# EagleSchematic.net
KiCad netlist of a schematic drawn in EAGLE
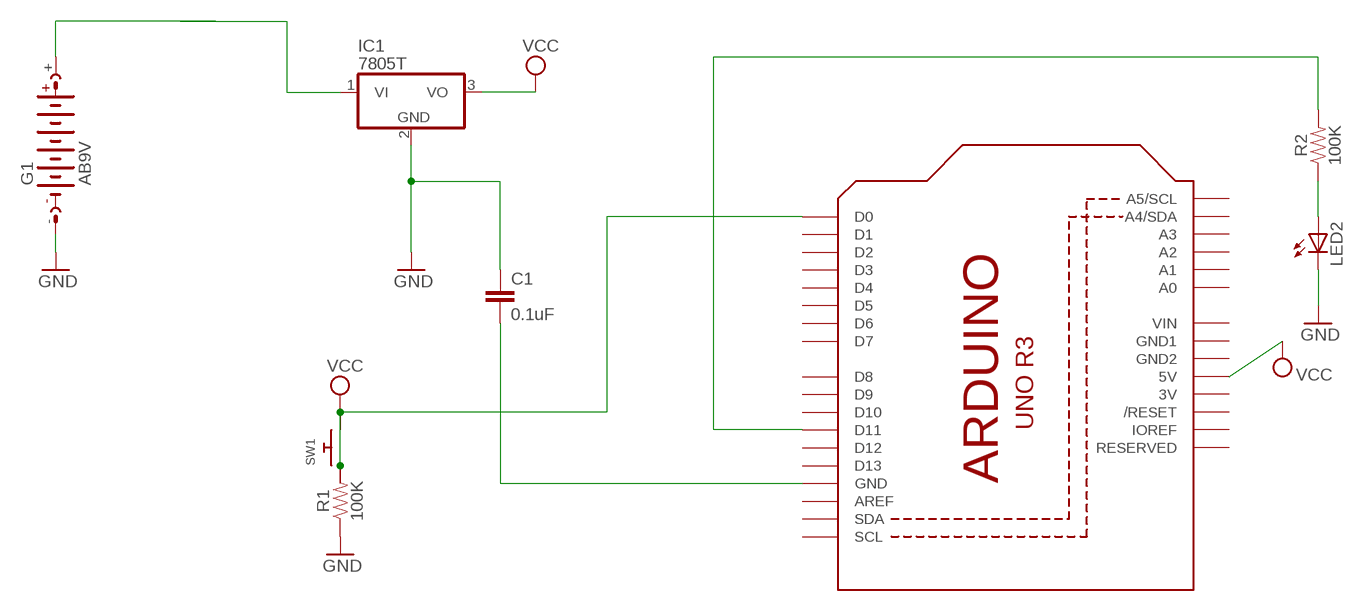
[diagram p0: schematic, sheet 1]

(export (version "E")
  (design (tool "Eeschema 10.0.6"))
  (components
    (comp (ref "C1")
      (value "0.1uF")
      (footprint "eagle-import:0402")
      (libsource (lib "eagle-import") (part "0.1UF-0402-16V-10%"))
    )
    (comp (ref "G1")
      (value "AB9V")
      (footprint "eagle-import:AB9V")
      (libsource (lib "eagle-import") (part "AB9V"))
    )
    (comp (ref "IC1")
      (value "7805T")
      (footprint "eagle-import:TO220H")
      (libsource (lib "eagle-import") (part "78T05"))
    )
    (comp (ref "LED2")
      (value "LED5MM")
      (footprint "eagle-import:LED5MM")
      (libsource (lib "eagle-import") (part "LED5MM"))
    )
    (comp (ref "R1")
      (value "100K")
      (footprint "eagle-import:0402")
      (libsource (lib "eagle-import") (part "100KOHM-0402-1/16W-1%"))
    )
    (comp (ref "R2")
      (value "100K")
      (footprint "eagle-import:0402")
      (libsource (lib "eagle-import") (part "100KOHM-0402-1/16W-1%"))
    )
    (comp (ref "SW1")
      (value "SWITCH_PUSHBUTTONSOFTTOUCHSMD_SJ")
      (footprint "eagle-import:PUSHBUTTON_SMD_SJ")
      (libsource (lib "eagle-import") (part "SWITCH_PUSHBUTTONSOFTTOUCHSMD_SJ"))
    )
    (comp (ref "U1")
      (value "ARDUINOR3-BPLACE")
      (footprint "eagle-import:ARDUINOR3-BPLACE")
      (libsource (lib "eagle-import") (part "ARDUINOR3-BPLACE"))
    )
  )
  (nets
    (net (code "1") (name "/3V") (class "Default")
      (node (ref "U1") (pin "3V") (pinfunction "3V_3V") (pintype "power_in"))
    )
    (net (code "2") (name "/GND1") (class "Default")
      (node (ref "U1") (pin "GND1") (pinfunction "GND1_GND1") (pintype "power_in"))
    )
    (net (code "3") (name "/GND2") (class "Default")
      (node (ref "U1") (pin "GND2") (pinfunction "GND2_GND2") (pintype "power_in"))
    )
    (net (code "4") (name "/VIN") (class "Default")
      (node (ref "U1") (pin "VIN") (pinfunction "VIN_VIN") (pintype "power_in"))
    )
    (net (code "5") (name "GND") (class "Default")
      (node (ref "C1") (pin "1") (pinfunction "1_1") (pintype "passive"))
      (node (ref "G1") (pin "-") (pinfunction "-_-") (pintype "passive"))
      (node (ref "IC1") (pin "2") (pinfunction "GND_2") (pintype "passive"))
      (node (ref "LED2") (pin "K") (pinfunction "C_K") (pintype "passive"))
      (node (ref "R1") (pin "1") (pinfunction "1_1") (pintype "passive"))
    )
    (net (code "6") (name "Net-(C1-Pad2)") (class "Default")
      (node (ref "C1") (pin "2") (pinfunction "2_2") (pintype "passive"))
      (node (ref "U1") (pin "GND") (pinfunction "GND_GND") (pintype "power_in"))
    )
    (net (code "7") (name "Net-(LED2-PadA)") (class "Default")
      (node (ref "LED2") (pin "A") (pinfunction "A_A") (pintype "passive"))
      (node (ref "R2") (pin "1") (pinfunction "1_1") (pintype "passive"))
    )
    (net (code "8") (name "Net-(R2-Pad2)") (class "Default")
      (node (ref "R2") (pin "2") (pinfunction "2_2") (pintype "passive"))
      (node (ref "U1") (pin "D11") (pinfunction "D11_D11") (pintype "bidirectional"))
    )
    (net (code "9") (name "VCC") (class "Default")
      (node (ref "IC1") (pin "3") (pinfunction "VO_3") (pintype "passive"))
      (node (ref "R1") (pin "2") (pinfunction "2_2") (pintype "passive"))
      (node (ref "SW1") (pin "P$2") (pinfunction "P$2_P$2") (pintype "passive"))
      (node (ref "U1") (pin "5V") (pinfunction "5V_5V") (pintype "power_in"))
      (node (ref "U1") (pin "D0") (pinfunction "D0_D0") (pintype "bidirectional"))
    )
    (net (code "10") (name "unconnected-(G1-Pad+)") (class "Default")
      (node (ref "G1") (pin "+") (pinfunction "+_+") (pintype "passive"))
    )
    (net (code "11") (name "unconnected-(IC1-VI-Pad1)") (class "Default")
      (node (ref "IC1") (pin "1") (pinfunction "VI_1") (pintype "input"))
    )
    (net (code "12") (name "unconnected-(SW1-PadP$1)") (class "Default")
      (node (ref "SW1") (pin "P$1") (pinfunction "P$1_P$1") (pintype "passive"))
    )
    (net (code "13") (name "unconnected-(U1-A4{slash}SDA-PadA4)") (class "Default")
      (node (ref "U1") (pin "A4") (pinfunction "A4/SDA_A4") (pintype "bidirectional"))
    )
    (net (code "14") (name "unconnected-(U1-A5{slash}SCL-PadA5)") (class "Default")
      (node (ref "U1") (pin "A5") (pinfunction "A5/SCL_A5") (pintype "bidirectional"))
    )
    (net (code "15") (name "unconnected-(U1-PadA0)") (class "Default")
      (node (ref "U1") (pin "A0") (pinfunction "A0_A0") (pintype "bidirectional"))
    )
    (net (code "16") (name "unconnected-(U1-PadA1)") (class "Default")
      (node (ref "U1") (pin "A1") (pinfunction "A1_A1") (pintype "bidirectional"))
    )
    (net (code "17") (name "unconnected-(U1-PadA2)") (class "Default")
      (node (ref "U1") (pin "A2") (pinfunction "A2_A2") (pintype "bidirectional"))
    )
    (net (code "18") (name "unconnected-(U1-PadA3)") (class "Default")
      (node (ref "U1") (pin "A3") (pinfunction "A3_A3") (pintype "bidirectional"))
    )
    (net (code "19") (name "unconnected-(U1-PadAREF)") (class "Default")
      (node (ref "U1") (pin "AREF") (pinfunction "AREF_AREF") (pintype "bidirectional"))
    )
    (net (code "20") (name "unconnected-(U1-PadD1)") (class "Default")
      (node (ref "U1") (pin "D1") (pinfunction "D1_D1") (pintype "bidirectional"))
    )
    (net (code "21") (name "unconnected-(U1-PadD2)") (class "Default")
      (node (ref "U1") (pin "D2") (pinfunction "D2_D2") (pintype "bidirectional"))
    )
    (net (code "22") (name "unconnected-(U1-PadD3)") (class "Default")
      (node (ref "U1") (pin "D3") (pinfunction "D3_D3") (pintype "bidirectional"))
    )
    (net (code "23") (name "unconnected-(U1-PadD4)") (class "Default")
      (node (ref "U1") (pin "D4") (pinfunction "D4_D4") (pintype "bidirectional"))
    )
    (net (code "24") (name "unconnected-(U1-PadD5)") (class "Default")
      (node (ref "U1") (pin "D5") (pinfunction "D5_D5") (pintype "bidirectional"))
    )
    (net (code "25") (name "unconnected-(U1-PadD6)") (class "Default")
      (node (ref "U1") (pin "D6") (pinfunction "D6_D6") (pintype "bidirectional"))
    )
    (net (code "26") (name "unconnected-(U1-PadD7)") (class "Default")
      (node (ref "U1") (pin "D7") (pinfunction "D7_D7") (pintype "bidirectional"))
    )
    (net (code "27") (name "unconnected-(U1-PadD8)") (class "Default")
      (node (ref "U1") (pin "D8") (pinfunction "D8_D8") (pintype "bidirectional"))
    )
    (net (code "28") (name "unconnected-(U1-PadD9)") (class "Default")
      (node (ref "U1") (pin "D9") (pinfunction "D9_D9") (pintype "bidirectional"))
    )
    (net (code "29") (name "unconnected-(U1-PadD10)") (class "Default")
      (node (ref "U1") (pin "D10") (pinfunction "D10_D10") (pintype "bidirectional"))
    )
    (net (code "30") (name "unconnected-(U1-PadD12)") (class "Default")
      (node (ref "U1") (pin "D12") (pinfunction "D12_D12") (pintype "bidirectional"))
    )
    (net (code "31") (name "unconnected-(U1-PadD13)") (class "Default")
      (node (ref "U1") (pin "D13") (pinfunction "D13_D13") (pintype "bidirectional"))
    )
    (net (code "32") (name "unconnected-(U1-PadIOREF)") (class "Default")
      (node (ref "U1") (pin "IOREF") (pinfunction "IOREF_IOREF") (pintype "output"))
    )
    (net (code "33") (name "unconnected-(U1-PadRESERVED)") (class "Default")
      (node (ref "U1") (pin "RESERVED") (pinfunction "RESERVED_RESERVED") (pintype "no_connect"))
    )
    (net (code "34") (name "unconnected-(U1-PadSCL)") (class "Default")
      (node (ref "U1") (pin "SCL") (pinfunction "SCL_SCL") (pintype "bidirectional"))
    )
    (net (code "35") (name "unconnected-(U1-PadSDA)") (class "Default")
      (node (ref "U1") (pin "SDA") (pinfunction "SDA_SDA") (pintype "bidirectional"))
    )
    (net (code "36") (name "unconnected-(U1-{slash}RESET-PadRESET)") (class "Default")
      (node (ref "U1") (pin "RESET") (pinfunction "/RESET_RESET") (pintype "bidirectional"))
    )
  )
)
